# SCH_Pocket_Jammer_2024-07-12.net
KiCad netlist of a schematic drawn in EasyEDA
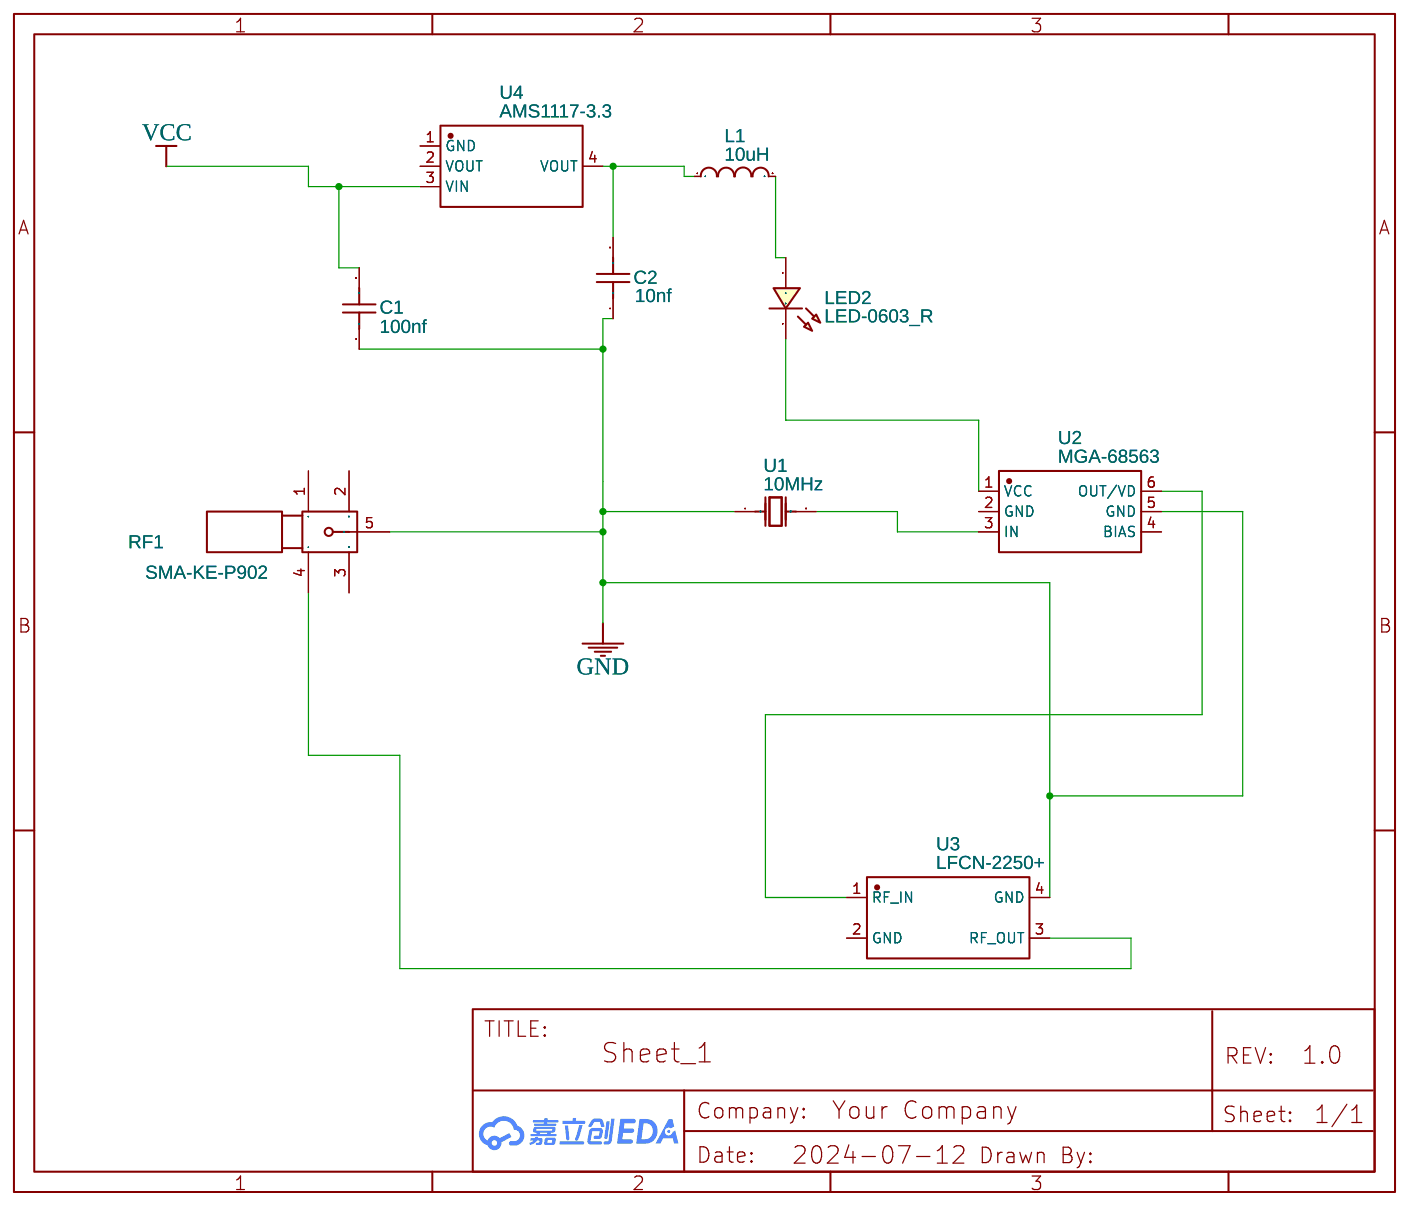
[diagram p0: schematic sheet]

(export (version "E")
  (design (tool "Eeschema 10.0.6"))
  (components
    (comp (ref "C1") (value "100nf") (libsource (lib "") (part "C_0603_US_1")))
    (comp (ref "C2") (value "10nf") (libsource (lib "") (part "C_0603_US")))
    (comp (ref "L1") (value "10uH") (libsource (lib "") (part "L0603_US")))
    (comp (ref "LED2")
      (value "LED-0603_R")
      (fields
        (field (name "BOM_Manufacturer Part") "19-217/R6C-AL1M2VY/3T")
        (field (name "BOM_Supplier Part") "C72044")
      )
      (libsource (lib "") (part "LED-0603_R"))
    )
    (comp (ref "RF1")
      (value "SMA-KE-P902")
      (fields (field (name "Manufacturer") "DreamLNK(骏晔科技)"))
      (libsource (lib "") (part "SMA-KE-P902"))
    )
    (comp (ref "U1")
      (value "10MHz")
      (fields (field (name "Manufacturer Part") "ECS-100-20-5PVX") (field (name "Manufacturer") "ECS"))
      (libsource (lib "") (part "ECS-100-20-5PVX"))
    )
    (comp (ref "U2")
      (value "MGA-68563")
      (fields (field (name "Manufacturer Part") "mga-68563"))
      (libsource (lib "") (part "MGA-68563"))
    )
    (comp (ref "U3") (value "LFCN-2250+") (libsource (lib "") (part "LFCN-2250+")))
    (comp (ref "U4")
      (value "AMS1117-3.3")
      (fields (field (name "Manufacturer") "AMS"))
      (libsource (lib "") (part "AMS1117-3.3"))
    )
  )
  (nets
    (net (code "1") (name "GND") (class "Default")
      (node (ref "C1") (pin "1") (pinfunction "1_1") (pintype "unspecified"))
      (node (ref "C2") (pin "1") (pinfunction "1_1") (pintype "unspecified"))
      (node (ref "RF1") (pin "5") (pinfunction "5_5") (pintype "unspecified"))
      (node (ref "U1") (pin "1") (pinfunction "OSC1_1") (pintype "input"))
      (node (ref "U2") (pin "5") (pinfunction "GND_5") (pintype "unspecified"))
      (node (ref "U3") (pin "4") (pinfunction "GND_4") (pintype "unspecified"))
    )
    (net (code "2") (name "Net-(C2-Pad2)") (class "Default")
      (node (ref "C2") (pin "2") (pinfunction "2_2") (pintype "unspecified"))
      (node (ref "L1") (pin "1") (pinfunction "1_1") (pintype "unspecified"))
      (node (ref "U4") (pin "4") (pinfunction "VOUT_4") (pintype "unspecified"))
    )
    (net (code "3") (name "Net-(L1-Pad2)") (class "Default")
      (node (ref "L1") (pin "2") (pinfunction "2_2") (pintype "unspecified"))
      (node (ref "LED2") (pin "1") (pinfunction "1_1") (pintype "unspecified"))
    )
    (net (code "4") (name "Net-(U1-OSC2)") (class "Default")
      (node (ref "U1") (pin "2") (pinfunction "OSC2_2") (pintype "input"))
      (node (ref "U2") (pin "3") (pinfunction "IN_3") (pintype "unspecified"))
    )
    (net (code "5") (name "Net-(U2-OUT{slash}VD)") (class "Default")
      (node (ref "U2") (pin "6") (pinfunction "OUT/VD_6") (pintype "unspecified"))
      (node (ref "U3") (pin "1") (pinfunction "RF_IN_1") (pintype "unspecified"))
    )
    (net (code "6") (name "Net-(U2-VCC)") (class "Default")
      (node (ref "LED2") (pin "2") (pinfunction "2_2") (pintype "unspecified"))
      (node (ref "U2") (pin "1") (pinfunction "VCC_1") (pintype "unspecified"))
    )
    (net (code "7") (name "Net-(U3-RF_OUT)") (class "Default")
      (node (ref "RF1") (pin "4") (pinfunction "4_4") (pintype "unspecified"))
      (node (ref "U3") (pin "3") (pinfunction "RF_OUT_3") (pintype "unspecified"))
    )
    (net (code "8") (name "VCC") (class "Default")
      (node (ref "C1") (pin "2") (pinfunction "2_2") (pintype "unspecified"))
      (node (ref "U4") (pin "3") (pinfunction "VIN_3") (pintype "unspecified"))
    )
    (net (code "9") (name "unconnected-(RF1-Pad1)") (class "Default")
      (node (ref "RF1") (pin "1") (pinfunction "1_1") (pintype "unspecified"))
    )
    (net (code "10") (name "unconnected-(RF1-Pad2)") (class "Default")
      (node (ref "RF1") (pin "2") (pinfunction "2_2") (pintype "unspecified"))
    )
    (net (code "11") (name "unconnected-(RF1-Pad3)") (class "Default")
      (node (ref "RF1") (pin "3") (pinfunction "3_3") (pintype "unspecified"))
    )
    (net (code "12") (name "unconnected-(U2-BIAS-Pad4)") (class "Default")
      (node (ref "U2") (pin "4") (pinfunction "BIAS_4") (pintype "unspecified"))
    )
    (net (code "13") (name "unconnected-(U2-GND-Pad2)") (class "Default")
      (node (ref "U2") (pin "2") (pinfunction "GND_2") (pintype "unspecified"))
    )
    (net (code "14") (name "unconnected-(U3-GND-Pad2)") (class "Default")
      (node (ref "U3") (pin "2") (pinfunction "GND_2") (pintype "unspecified"))
    )
    (net (code "15") (name "unconnected-(U4-GND-Pad1)") (class "Default")
      (node (ref "U4") (pin "1") (pinfunction "GND_1") (pintype "unspecified"))
    )
    (net (code "16") (name "unconnected-(U4-VOUT-Pad2)") (class "Default")
      (node (ref "U4") (pin "2") (pinfunction "VOUT_2") (pintype "unspecified"))
    )
  )
)
